# FOTA_MicroController_Core.net
KiCad netlist of a schematic drawn in Altium Designer
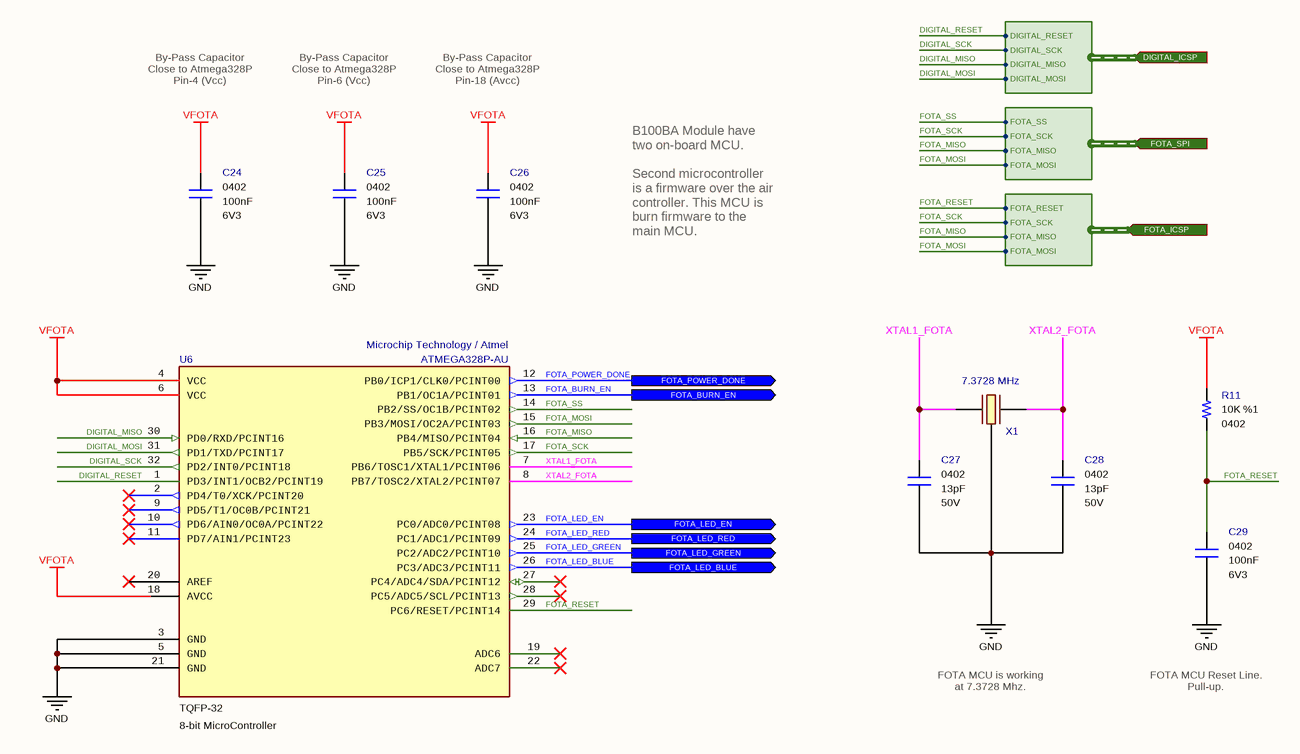
[diagram p0: FOTA MicroController Core.SchDoc]

(export (version "E")
  (design (tool "Eeschema 10.0.6"))
  (components
    (comp (ref "C24")
      (value "100nF")
      (footprint "CAPACITOR_0402")
      (description "Capacitor - 100nF [0402-6V3] (Ceramic)")
      (fields
        (field (name "TOLERANCE") "%10")
        (field (name "CASE") "0402")
        (field (name "VOLTAGE") "6V3")
        (field (name "MANUFACTURER PART NUMBER") "04026D104KAT4A")
      )
      (libsource (lib "Ovoo_Library") (part "Capacitor - 100nF [0402-6V3]"))
    )
    (comp (ref "C25")
      (value "100nF")
      (footprint "CAPACITOR_0402")
      (description "Capacitor - 100nF [0402-6V3] (Ceramic)")
      (fields
        (field (name "TOLERANCE") "%10")
        (field (name "CASE") "0402")
        (field (name "VOLTAGE") "6V3")
        (field (name "MANUFACTURER PART NUMBER") "04026D104KAT4A")
      )
      (libsource (lib "Ovoo_Library") (part "Capacitor - 100nF [0402-6V3]"))
    )
    (comp (ref "C26")
      (value "100nF")
      (footprint "CAPACITOR_0402")
      (description "Capacitor - 100nF [0402-6V3] (Ceramic)")
      (fields
        (field (name "TOLERANCE") "%10")
        (field (name "CASE") "0402")
        (field (name "VOLTAGE") "6V3")
        (field (name "MANUFACTURER PART NUMBER") "04026D104KAT4A")
      )
      (libsource (lib "Ovoo_Library") (part "Capacitor - 100nF [0402-6V3]"))
    )
    (comp (ref "C27")
      (value "13pF")
      (footprint "CAPACITOR_0402")
      (description "Capacitor - 13pF [0402] (Ceramic)")
      (fields
        (field (name "TOLERANCE") "1%")
        (field (name "VOLTAGE") "50V")
        (field (name "CASE") "0402")
        (field (name "MANUFACTURER PART NUMBER") "CBR04C130F5GAC")
      )
      (libsource (lib "Ovoo_Library") (part "Capacitor - 13pF [0402-50V]"))
    )
    (comp (ref "C28")
      (value "13pF")
      (footprint "CAPACITOR_0402")
      (description "Capacitor - 13pF [0402] (Ceramic)")
      (fields
        (field (name "TOLERANCE") "1%")
        (field (name "VOLTAGE") "50V")
        (field (name "CASE") "0402")
        (field (name "MANUFACTURER PART NUMBER") "CBR04C130F5GAC")
      )
      (libsource (lib "Ovoo_Library") (part "Capacitor - 13pF [0402-50V]"))
    )
    (comp (ref "C29")
      (value "100nF")
      (footprint "CAPACITOR_0402")
      (description "Capacitor - 100nF [0402-6V3] (Ceramic)")
      (fields
        (field (name "TOLERANCE") "%10")
        (field (name "CASE") "0402")
        (field (name "VOLTAGE") "6V3")
        (field (name "MANUFACTURER PART NUMBER") "04026D104KAT4A")
      )
      (libsource (lib "Ovoo_Library") (part "Capacitor - 100nF [0402-6V3]"))
    )
    (comp (ref "R11")
      (value "10K")
      (footprint "RESISTOR_0402")
      (description "Thick Film Resistors - SMD 1/16 W 10 Kohms 1%")
      (fields
        (field (name "TOLERANCE") "%1")
        (field (name "CASE") "0402")
        (field (name "MANUFACTURER PART NUMBER") "CRCW040210K0FKED")
        (field (name "MOUSER PART NUMBER") "71-CRCW0402-10K-E3")
      )
      (libsource (lib "Ovoo_Library") (part "Resistor - 10K"))
    )
    (comp (ref "U6")
      (value "8-bit MicroController")
      (footprint "TQFP32")
      (description "8-bit Microcontrollers - MCU 32KB In-system Flash 20MHz 1.8V-5.5V")
      (fields
        (field (name "CASE") "TQFP-32")
        (field (name "MOUSER PART NUMBER") "556-ATMEGA328P-AU")
        (field (name "MANUFACTURER PART NUMBER") "ATMEGA328P-AU")
        (field (name "MANUFACTURER NAME") "Microchip Technology / Atmel")
      )
      (libsource (lib "Ovoo_Library") (part "IC - ATMEGA328P"))
    )
    (comp (ref "X1")
      (value "7.3728 MHz")
      (footprint "ABRACON_CRYSTAL")
      (description "Crystals 7.3728MHz 18pF -40C +85C")
      (fields
        (field (name "TOLERANCE") "20 ppm")
        (field (name "MANUFACTURER PART NUMBER") "ABMM2-7.3728MHZ-E2-T")
      )
      (libsource (lib "Ovoo_Library") (part "Crystal - 7.3728 MHz (Abracon)"))
    )
  )
  (nets
    (net (code "4") (name "/DIGITAL_MISO") (class "Default")
      (node (ref "U6") (pin "30") (pinfunction "PD0/RXD/PCINT16_30") (pintype "input"))
    )
    (net (code "5") (name "/DIGITAL_MOSI") (class "Default")
      (node (ref "U6") (pin "31") (pinfunction "PD1/TXD/PCINT17_31") (pintype "output"))
    )
    (net (code "6") (name "/DIGITAL_RESET") (class "Default")
      (node (ref "U6") (pin "1") (pinfunction "PD3/INT1/OCB2/PCINT19_1") (pintype "passive"))
    )
    (net (code "7") (name "/DIGITAL_SCK") (class "Default")
      (node (ref "U6") (pin "32") (pinfunction "PD2/INT0/PCINT18_32") (pintype "output"))
    )
    (net (code "8") (name "/FOTA_BURN_EN") (class "Default")
      (node (ref "U6") (pin "13") (pinfunction "PB1/OC1A/PCINT01_13") (pintype "output"))
    )
    (net (code "9") (name "/FOTA_LED_BLUE") (class "Default")
      (node (ref "U6") (pin "26") (pinfunction "PC3/ADC3/PCINT11_26") (pintype "output"))
    )
    (net (code "10") (name "/FOTA_LED_EN") (class "Default")
      (node (ref "U6") (pin "23") (pinfunction "PC0/ADC0/PCINT08_23") (pintype "output"))
    )
    (net (code "11") (name "/FOTA_LED_GREEN") (class "Default")
      (node (ref "U6") (pin "25") (pinfunction "PC2/ADC2/PCINT10_25") (pintype "output"))
    )
    (net (code "12") (name "/FOTA_LED_RED") (class "Default")
      (node (ref "U6") (pin "24") (pinfunction "PC1/ADC1/PCINT09_24") (pintype "output"))
    )
    (net (code "13") (name "/FOTA_MISO") (class "Default")
      (node (ref "U6") (pin "16") (pinfunction "PB4/MISO/PCINT04_16") (pintype "input"))
    )
    (net (code "14") (name "/FOTA_MOSI") (class "Default")
      (node (ref "U6") (pin "15") (pinfunction "PB3/MOSI/OC2A/PCINT03_15") (pintype "output"))
    )
    (net (code "15") (name "/FOTA_POWER_DONE") (class "Default")
      (node (ref "U6") (pin "12") (pinfunction "PB0/ICP1/CLK0/PCINT00_12") (pintype "output"))
    )
    (net (code "16") (name "/FOTA_RESET") (class "Default")
      (node (ref "C29") (pin "2") (pinfunction "2_2") (pintype "passive"))
      (node (ref "R11") (pin "1") (pinfunction "1_1") (pintype "passive"))
      (node (ref "U6") (pin "29") (pinfunction "PC6/RESET/PCINT14_29") (pintype "passive"))
    )
    (net (code "17") (name "/FOTA_SCK") (class "Default")
      (node (ref "U6") (pin "17") (pinfunction "PB5/SCK/PCINT05_17") (pintype "output"))
    )
    (net (code "18") (name "/FOTA_SS") (class "Default")
      (node (ref "U6") (pin "14") (pinfunction "PB2/SS/OC1B/PCINT02_14") (pintype "output"))
    )
    (net (code "19") (name "/XTAL1_FOTA") (class "Default")
      (node (ref "C27") (pin "2") (pinfunction "2_2") (pintype "passive"))
      (node (ref "U6") (pin "7") (pinfunction "PB6/TOSC1/XTAL1/PCINT06_7") (pintype "passive"))
      (node (ref "X1") (pin "3") (pinfunction "OUT/IN_3") (pintype "passive"))
    )
    (net (code "20") (name "/XTAL2_FOTA") (class "Default")
      (node (ref "C28") (pin "2") (pinfunction "2_2") (pintype "passive"))
      (node (ref "U6") (pin "8") (pinfunction "PB7/TOSC2/XTAL2/PCINT07_8") (pintype "passive"))
      (node (ref "X1") (pin "1") (pinfunction "IN/OUT_1") (pintype "passive"))
    )
    (net (code "24") (name "GND") (class "Default")
      (node (ref "C24") (pin "1") (pinfunction "1_1") (pintype "passive"))
      (node (ref "C25") (pin "1") (pinfunction "1_1") (pintype "passive"))
      (node (ref "C26") (pin "1") (pinfunction "1_1") (pintype "passive"))
      (node (ref "C27") (pin "1") (pinfunction "1_1") (pintype "passive"))
      (node (ref "C28") (pin "1") (pinfunction "1_1") (pintype "passive"))
      (node (ref "C29") (pin "1") (pinfunction "1_1") (pintype "passive"))
      (node (ref "U6") (pin "21") (pinfunction "GND_21") (pintype "power_in"))
      (node (ref "U6") (pin "3") (pinfunction "GND_3") (pintype "power_in"))
      (node (ref "U6") (pin "5") (pinfunction "GND_5") (pintype "power_in"))
      (node (ref "X1") (pin "2") (pinfunction "GND_2") (pintype "passive"))
    )
    (net (code "25") (name "VFOTA") (class "Default")
      (node (ref "C24") (pin "2") (pinfunction "2_2") (pintype "passive"))
      (node (ref "C25") (pin "2") (pinfunction "2_2") (pintype "passive"))
      (node (ref "C26") (pin "2") (pinfunction "2_2") (pintype "passive"))
      (node (ref "R11") (pin "2") (pinfunction "2_2") (pintype "passive"))
      (node (ref "U6") (pin "18") (pinfunction "AVCC_18") (pintype "passive"))
      (node (ref "U6") (pin "4") (pinfunction "VCC_4") (pintype "power_in"))
      (node (ref "U6") (pin "6") (pinfunction "VCC_6") (pintype "power_in"))
    )
    (net (code "26") (name "unconnected-(U6-ADC6-Pad19)") (class "Default")
      (node (ref "U6") (pin "19") (pinfunction "ADC6_19") (pintype "passive+no_connect"))
    )
    (net (code "27") (name "unconnected-(U6-ADC7-Pad22)") (class "Default")
      (node (ref "U6") (pin "22") (pinfunction "ADC7_22") (pintype "passive+no_connect"))
    )
    (net (code "28") (name "unconnected-(U6-AREF-Pad20)") (class "Default")
      (node (ref "U6") (pin "20") (pinfunction "AREF_20") (pintype "passive+no_connect"))
    )
    (net (code "29") (name "unconnected-(U6-PC4{slash}ADC4{slash}SDA{slash}PCINT12-Pad27)") (class "Default")
      (node (ref "U6") (pin "27") (pinfunction "PC4/ADC4/SDA/PCINT12_27") (pintype "bidirectional+no_connect"))
    )
    (net (code "30") (name "unconnected-(U6-PC5{slash}ADC5{slash}SCL{slash}PCINT13-Pad28)") (class "Default")
      (node (ref "U6") (pin "28") (pinfunction "PC5/ADC5/SCL/PCINT13_28") (pintype "output+no_connect"))
    )
    (net (code "31") (name "unconnected-(U6-PD4{slash}T0{slash}XCK{slash}PCINT20-Pad2)") (class "Default")
      (node (ref "U6") (pin "2") (pinfunction "PD4/T0/XCK/PCINT20_2") (pintype "output+no_connect"))
    )
    (net (code "32") (name "unconnected-(U6-PD5{slash}T1{slash}OC0B{slash}PCINT21-Pad9)") (class "Default")
      (node (ref "U6") (pin "9") (pinfunction "PD5/T1/OC0B/PCINT21_9") (pintype "output+no_connect"))
    )
    (net (code "33") (name "unconnected-(U6-PD6{slash}AIN0{slash}OC0A{slash}PCINT22-Pad10)") (class "Default")
      (node (ref "U6") (pin "10") (pinfunction "PD6/AIN0/OC0A/PCINT22_10") (pintype "output+no_connect"))
    )
    (net (code "34") (name "unconnected-(U6-PD7{slash}AIN1{slash}PCINT23-Pad11)") (class "Default")
      (node (ref "U6") (pin "11") (pinfunction "PD7/AIN1/PCINT23_11") (pintype "passive+no_connect"))
    )
    (net (code "35") (name "unconnected-(X1-GND-Pad4)") (class "Default")
      (node (ref "X1") (pin "4") (pinfunction "GND_4") (pintype "passive"))
    )
  )
)
